# S7CAS-PLEIADES-CARTE-MERE_P07_TITLE.net
KiCad netlist of a schematic drawn in Altium Designer
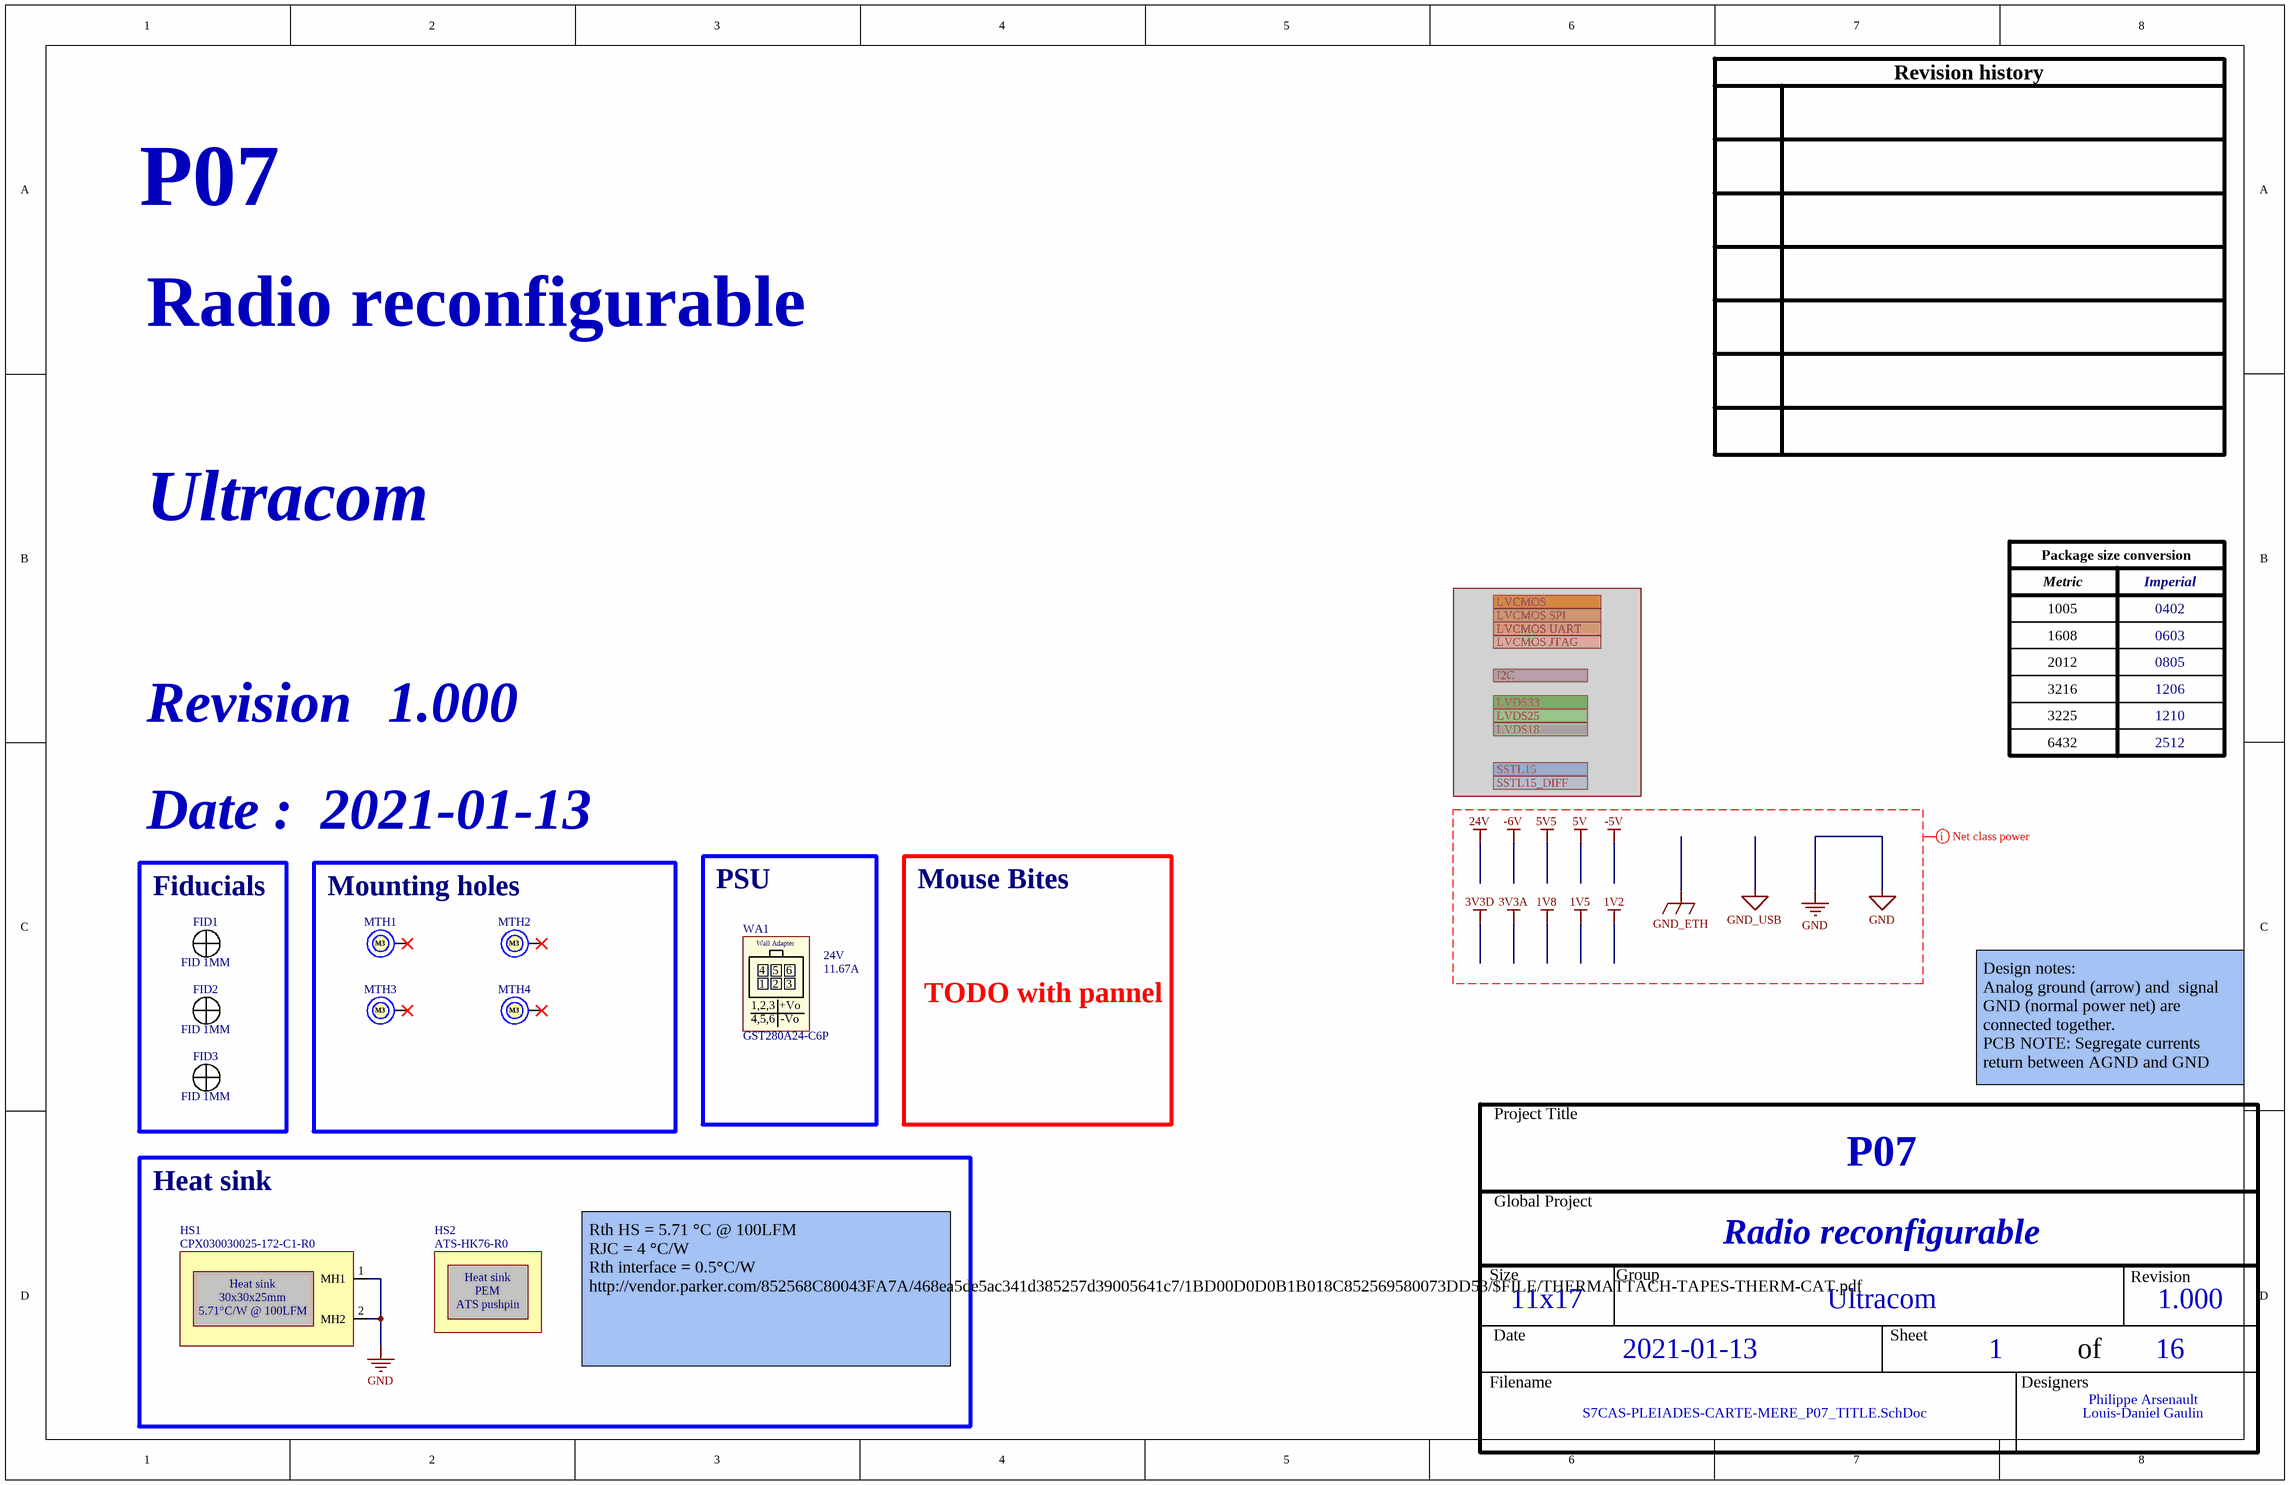
[diagram p0: S7CAS-PLEIADES-CARTE-MERE_P07_TITLE.SchDoc]

(export (version "E")
  (design (tool "Eeschema 10.0.6"))
  (components
    (comp (ref "FID1")
      (value "FID 1MM")
      (footprint "FID_CIRCLE_1MM")
      (description "FID - FIDUCIAL 1MM CIRCLE DOUBLE-SIDED - 1MM")
      (fields
        (field (name "CREATEDBY/DATE") "Jonathan Bouchard 2018-07-23")
        (field (name "VERIFIEDBY") "Caroline Paulin - 25 juillet 2018")
      )
      (libsource (lib "S7CAS_LIB2021") (part "FID_CIRCLE_1MM"))
    )
    (comp (ref "FID2")
      (value "FID 1MM")
      (footprint "FID_CIRCLE_1MM")
      (description "FID - FIDUCIAL 1MM CIRCLE DOUBLE-SIDED - 1MM")
      (fields
        (field (name "CREATEDBY/DATE") "Jonathan Bouchard 2018-07-23")
        (field (name "VERIFIEDBY") "Caroline Paulin - 25 juillet 2018")
      )
      (libsource (lib "S7CAS_LIB2021") (part "FID_CIRCLE_1MM"))
    )
    (comp (ref "FID3")
      (value "FID 1MM")
      (footprint "FID_CIRCLE_1MM")
      (description "FID - FIDUCIAL 1MM CIRCLE DOUBLE-SIDED - 1MM")
      (fields
        (field (name "CREATEDBY/DATE") "Jonathan Bouchard 2018-07-23")
        (field (name "VERIFIEDBY") "Caroline Paulin - 25 juillet 2018")
      )
      (libsource (lib "S7CAS_LIB2021") (part "FID_CIRCLE_1MM"))
    )
    (comp (ref "HS1")
      (value "CPX030030025-172-C1-R0")
      (footprint "THE_HS_ATS-CPX030030025-172-C1-R0")
      (description "THE_HS - Heat Sink 30x30x25 mm - TH")
      (libsource (lib "S7CAS_P07") (part "THE_HS_ATS-CPX030030025-172-C1-R0"))
    )
    (comp (ref "HS2")
      (value "ATS-HK76-R0")
      (footprint "THE_HS_ATS-CPX030030025-172-C1-R0")
      (description "MEC - Heat Sink PEM - TH")
      (libsource (lib "S7CAS_P07") (part "MEC_ATS-HK76-R0"))
    )
    (comp (ref "MTH1")
      (value "M3")
      (footprint "MTH_M3")
      (description "MTH - MOUNTING HOLE M3 PLATED - M3")
      (fields
        (field (name "CREATEDBY/DATE") "Jonathan Bouchard 2018-07-23")
        (field (name "VERIFIEDBY") "Arnaud Samson 23-07-18")
      )
      (libsource (lib "S7CAS_LIB2021") (part "MTH_M3"))
    )
    (comp (ref "MTH2")
      (value "M3")
      (footprint "MTH_M3")
      (description "MTH - MOUNTING HOLE M3 PLATED - M3")
      (fields
        (field (name "CREATEDBY/DATE") "Jonathan Bouchard 2018-07-23")
        (field (name "VERIFIEDBY") "Arnaud Samson 23-07-18")
      )
      (libsource (lib "S7CAS_LIB2021") (part "MTH_M3"))
    )
    (comp (ref "MTH3")
      (value "M3")
      (footprint "MTH_M3")
      (description "MTH - MOUNTING HOLE M3 PLATED - M3")
      (fields
        (field (name "CREATEDBY/DATE") "Jonathan Bouchard 2018-07-23")
        (field (name "VERIFIEDBY") "Arnaud Samson 23-07-18")
      )
      (libsource (lib "S7CAS_LIB2021") (part "MTH_M3"))
    )
    (comp (ref "MTH4")
      (value "M3")
      (footprint "MTH_M3")
      (description "MTH - MOUNTING HOLE M3 PLATED - M3")
      (fields
        (field (name "CREATEDBY/DATE") "Jonathan Bouchard 2018-07-23")
        (field (name "VERIFIEDBY") "Arnaud Samson 23-07-18")
      )
      (libsource (lib "S7CAS_LIB2021") (part "MTH_M3"))
    )
    (comp (ref "WA1")
      (value "GST280A24-C6P")
      (footprint "Model Name")
      (description "UND - AC/DC DESKTOP ADAPTER 24V 280W - MEC")
      (fields
        (field (name "TOLERANCE") "±3%")
        (field (name "CURRENT RATING") "11.67A")
        (field (name "ALTIUM_VALUE") "24V")
        (field (name "CREATEDBY/DATE") "Caroline Paulin - 5 avril 2019")
        (field (name "VERIFIEDBY") "Nicolas V. (2019-07-05)")
      )
      (libsource (lib "S7CAS_LIB2021") (part "UND_GST280A24-C6P"))
    )
  )
  (nets
    (net (code "21") (name "GND") (class "Default")
      (node (ref "HS1") (pin "1") (pinfunction "MH1_1") (pintype "passive"))
      (node (ref "HS1") (pin "2") (pinfunction "MH2_2") (pintype "passive"))
    )
    (net (code "24") (name "unconnected-(FID1-Pad1)") (class "Default")
      (node (ref "FID1") (pin "1") (pinfunction "1_1") (pintype "passive"))
    )
    (net (code "25") (name "unconnected-(FID1-Pad2)") (class "Default")
      (node (ref "FID1") (pin "2") (pinfunction "2_2") (pintype "passive"))
    )
    (net (code "26") (name "unconnected-(FID2-Pad1)") (class "Default")
      (node (ref "FID2") (pin "1") (pinfunction "1_1") (pintype "passive"))
    )
    (net (code "27") (name "unconnected-(FID2-Pad2)") (class "Default")
      (node (ref "FID2") (pin "2") (pinfunction "2_2") (pintype "passive"))
    )
    (net (code "28") (name "unconnected-(FID3-Pad1)") (class "Default")
      (node (ref "FID3") (pin "1") (pinfunction "1_1") (pintype "passive"))
    )
    (net (code "29") (name "unconnected-(FID3-Pad2)") (class "Default")
      (node (ref "FID3") (pin "2") (pinfunction "2_2") (pintype "passive"))
    )
    (net (code "30") (name "unconnected-(MTH1-Pad1)") (class "Default")
      (node (ref "MTH1") (pin "1") (pinfunction "1_1") (pintype "passive+no_connect"))
    )
    (net (code "31") (name "unconnected-(MTH2-Pad1)") (class "Default")
      (node (ref "MTH2") (pin "1") (pinfunction "1_1") (pintype "passive+no_connect"))
    )
    (net (code "32") (name "unconnected-(MTH3-Pad1)") (class "Default")
      (node (ref "MTH3") (pin "1") (pinfunction "1_1") (pintype "passive+no_connect"))
    )
    (net (code "33") (name "unconnected-(MTH4-Pad1)") (class "Default")
      (node (ref "MTH4") (pin "1") (pinfunction "1_1") (pintype "passive+no_connect"))
    )
  )
)
